# MODULATOR.net
KiCad netlist of a schematic drawn in Altium Designer
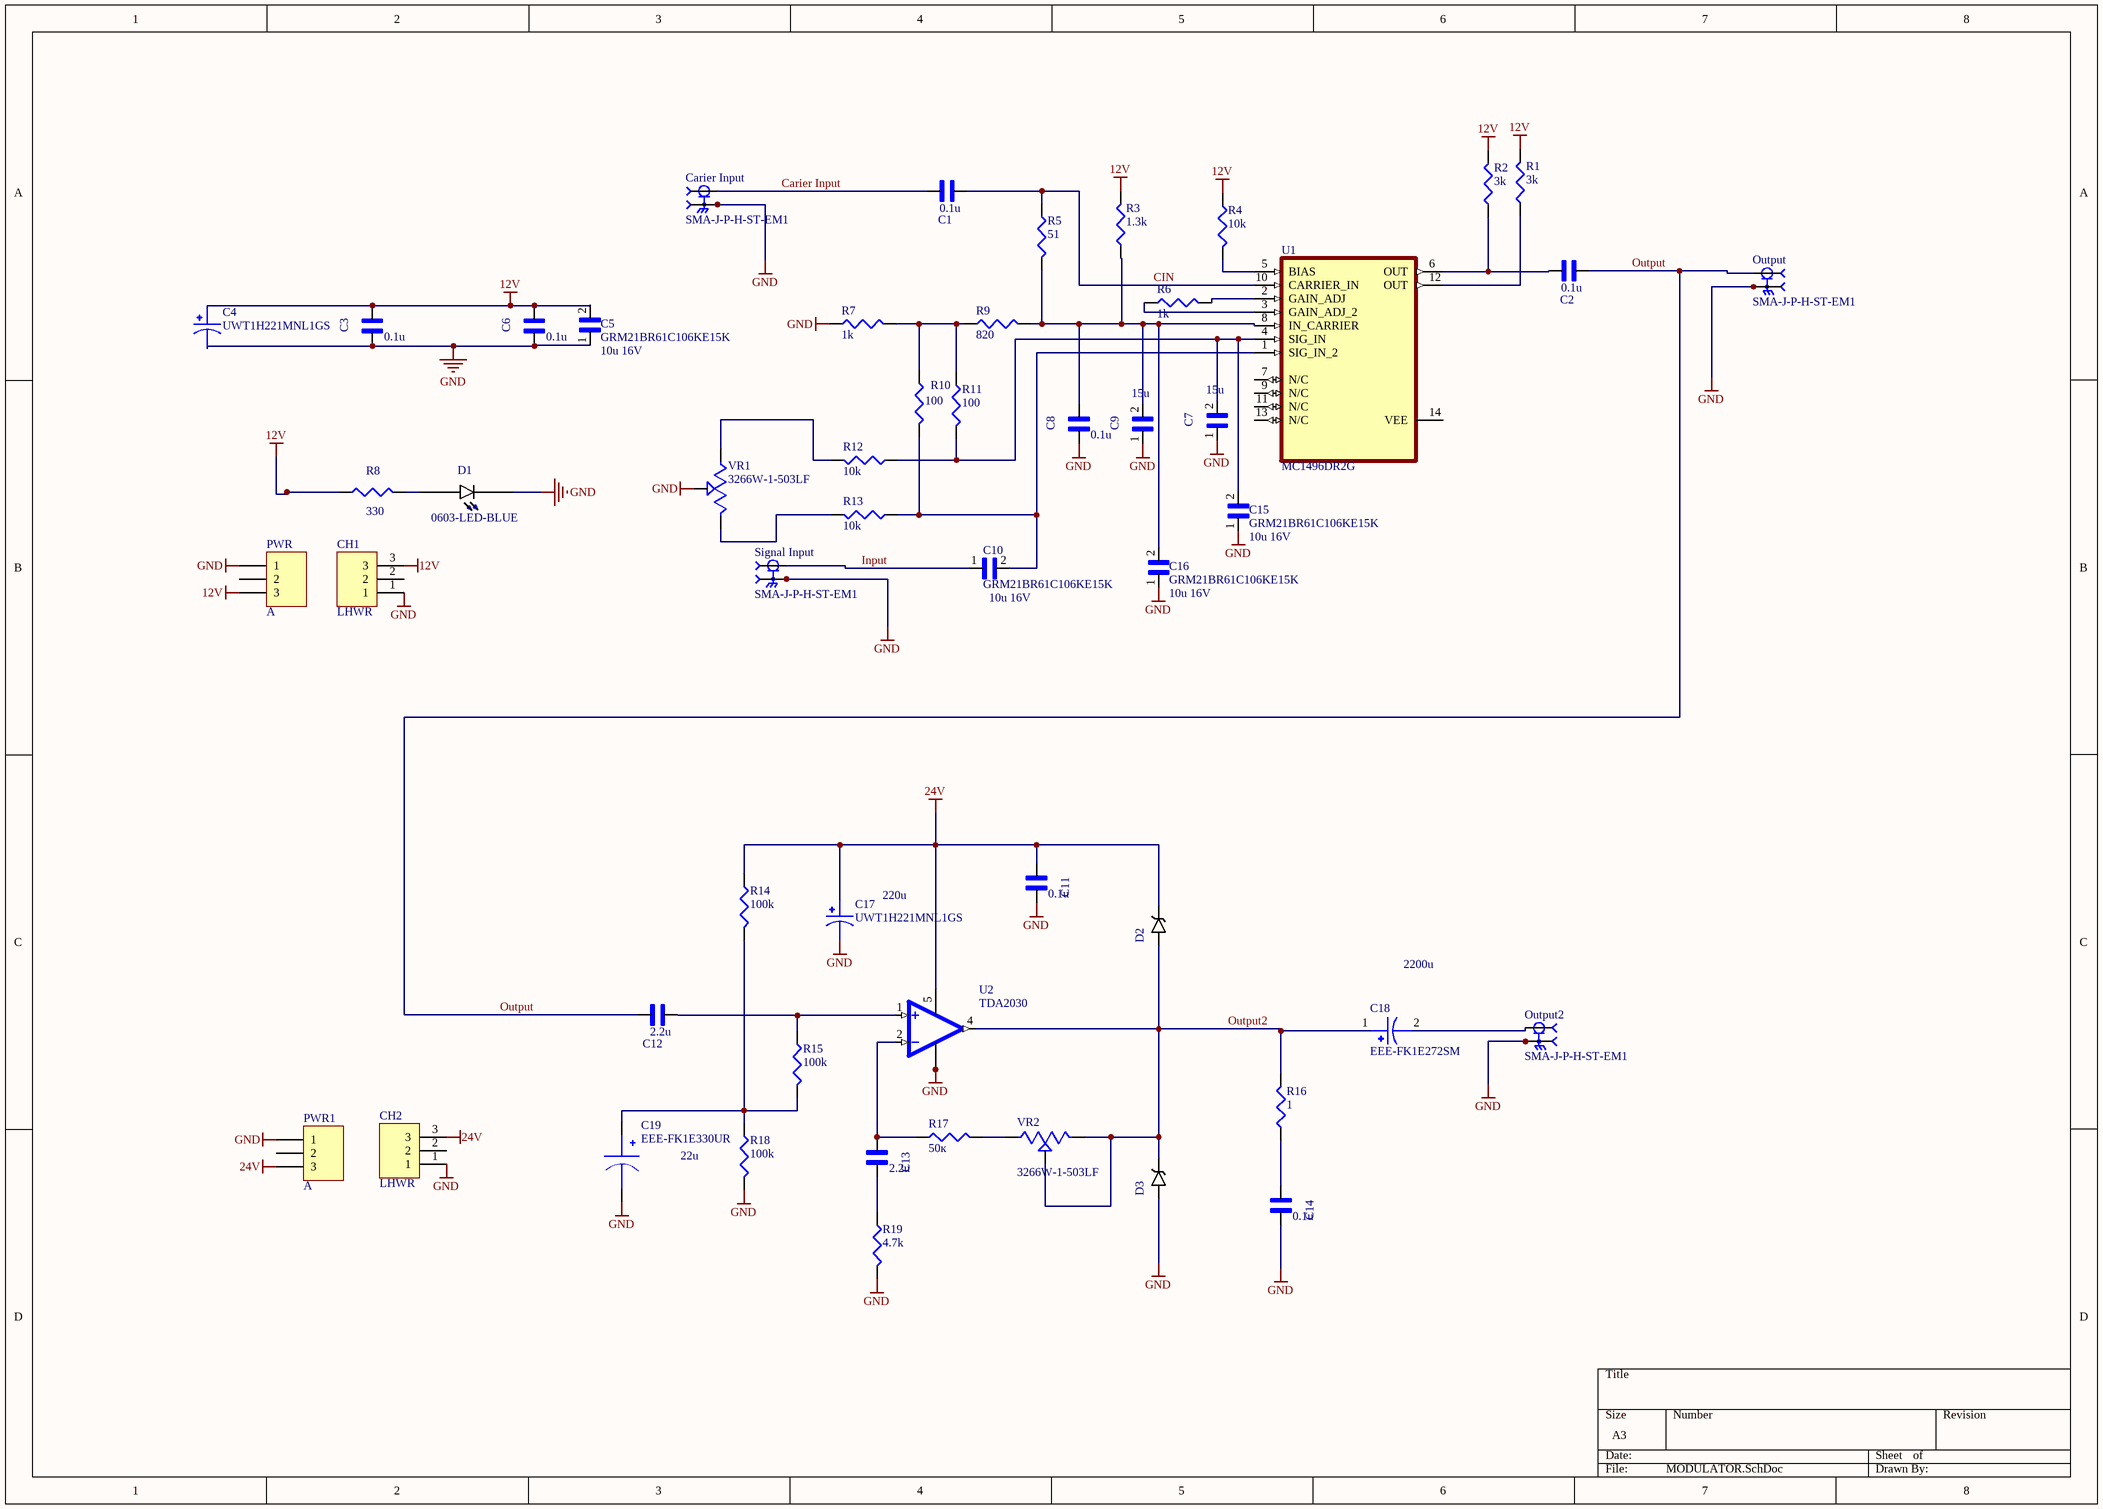
[diagram p0: MODULATOR.SchDoc]

(export (version "E")
  (design (tool "Eeschema 10.0.6"))
  (components
    (comp (ref "C1")
      (value "0.1u")
      (footprint "*CAPC1608X90")
      (description "Cap Thin Film 0.1uf 50v 0603")
      (fields (field (name "MF") "AVX") (field (name "MP") "GX035C104MAT2-500"))
      (libsource (lib "lib") (part "GX035C104MAT2-500"))
    )
    (comp (ref "C2")
      (value "0.1u")
      (footprint "*CAPC1608X90")
      (description "Cap Thin Film 0.1uf 50v 0603")
      (fields (field (name "MF") "AVX") (field (name "MP") "GX035C104MAT2-500"))
      (libsource (lib "lib") (part "GX035C104MAT2-500"))
    )
    (comp (ref "C3")
      (value "0.1u")
      (footprint "*CAPC1608X90")
      (description "Cap Thin Film 0.1uf 50v 0603")
      (fields (field (name "MF") "AVX") (field (name "MP") "GX035C104MAT2-500 or CL10B104JB8NNNC"))
      (libsource (lib "lib") (part "GX035C104MAT2-500"))
    )
    (comp (ref "C4")
      (value "UWT1H221MNL1GS")
      (footprint "CAPAE1030X1080N_UWT1H221MNL1GS")
      (description "220ВµF 50V Aluminum Electrolytic Capacitors Radial, Can - SMD 5000 Hrs @ 105В°C")
      (fields (field (name "MF") "{'manufacturer': u'Nichicon'}"))
      (libsource (lib "SnapEDA_Library") (part "UWT1H221MNL1GS"))
    )
    (comp (ref "C5")
      (value "GRM21BR61C106KE15K")
      (footprint "CAPC2012X135N")
      (fields (field (name "MF") "{'manufacturer': u'Murata'}") (field (name "ALTIUM_VALUE") "10u 16V"))
      (libsource (lib "") (part "GRM21BR61C106KE15K_1"))
    )
    (comp (ref "C6")
      (value "0.1u")
      (footprint "*CAPC1608X90")
      (description "Cap Thin Film 0.1uf 50v 0603")
      (fields (field (name "MF") "AVX") (field (name "MP") "GX035C104MAT2-500 or CL10B104JB8NNNC"))
      (libsource (lib "lib") (part "GX035C104MAT2-500"))
    )
    (comp (ref "C7")
      (value "15u")
      (footprint "*CAPC3216X125N")
      (description "Multilayer Ceramic Capacitor, GRM Series, 47 - F, - 10%, X5R, 10 V, 1206 [3216 Metric]")
      (fields (field (name "MF") "Murata Electronics") (field (name "MP") "GRM31CR61A476KE15L"))
      (libsource (lib "lib") (part "GRM31CR61A476KE15L"))
    )
    (comp (ref "C8")
      (value "0.1u")
      (footprint "*CAPC1608X90")
      (description "Cap Thin Film 0.1uf 50v 0603")
      (fields (field (name "MF") "AVX") (field (name "MP") "GX035C104MAT2-500"))
      (libsource (lib "lib") (part "GX035C104MAT2-500"))
    )
    (comp (ref "C9")
      (value "15u")
      (footprint "*CAPC3216X125N")
      (description "Multilayer Ceramic Capacitor, GRM Series, 47 - F, - 10%, X5R, 10 V, 1206 [3216 Metric]")
      (fields (field (name "MF") "Murata Electronics") (field (name "MP") "GRM31CR61A476KE15L"))
      (libsource (lib "lib") (part "GRM31CR61A476KE15L"))
    )
    (comp (ref "C10")
      (value "GRM21BR61C106KE15K")
      (footprint "CAPC2012X135N")
      (fields (field (name "MF") "{'manufacturer': u'Murata'}") (field (name "ALTIUM_VALUE") "10u 16V"))
      (libsource (lib "SnapEDA_Library") (part "GRM21BR61C106KE15K"))
    )
    (comp (ref "C11")
      (value "0.1u")
      (footprint "*CAPC1608X90")
      (description "Cap Thin Film 0.1uf 50v 0603")
      (fields (field (name "MF") "AVX") (field (name "MP") "GX035C104MAT2-500"))
      (libsource (lib "lib") (part "GX035C104MAT2-500"))
    )
    (comp (ref "C12")
      (value "2.2u")
      (footprint "*CAP3216X125N")
      (description "1206 2.2 uF 50 V В±10% Tolerance X7R SMT Multilayer Ceramic Capacitor")
      (fields (field (name "MF") "Murata Electronics") (field (name "MP") "GRM31CR71H225KA88L"))
      (libsource (lib "lib") (part "GRM31CR71H225KA88L"))
    )
    (comp (ref "C13")
      (value "2.2u")
      (footprint "*CAP3216X125N")
      (description "1206 2.2 uF 50 V В±10% Tolerance X7R SMT Multilayer Ceramic Capacitor")
      (fields (field (name "MF") "Murata Electronics") (field (name "MP") "GRM31CR71H225KA88L"))
      (libsource (lib "lib") (part "GRM31CR71H225KA88L"))
    )
    (comp (ref "C14")
      (value "0.1u")
      (footprint "*CAPC1608X90")
      (description "Cap Thin Film 0.1uf 50v 0603")
      (fields (field (name "MF") "AVX") (field (name "MP") "GX035C104MAT2-500"))
      (libsource (lib "lib") (part "GX035C104MAT2-500"))
    )
    (comp (ref "C15")
      (value "GRM21BR61C106KE15K")
      (footprint "CAPC2012X135N")
      (fields (field (name "MF") "{'manufacturer': u'Murata'}") (field (name "ALTIUM_VALUE") "10u 16V"))
      (libsource (lib "") (part "GRM21BR61C106KE15K_1"))
    )
    (comp (ref "C16")
      (value "GRM21BR61C106KE15K")
      (footprint "CAPC2012X135N")
      (fields (field (name "MF") "{'manufacturer': u'Murata'}") (field (name "ALTIUM_VALUE") "10u 16V"))
      (libsource (lib "") (part "GRM21BR61C106KE15K_1"))
    )
    (comp (ref "C17")
      (value "UWT1H221MNL1GS")
      (footprint "CAPAE1030X1080N_UWT1H221MNL1GS")
      (description "220ВµF 50V Aluminum Electrolytic Capacitors Radial, Can - SMD 5000 Hrs @ 105В°C")
      (fields (field (name "MF") "{'manufacturer': u'Nichicon'}"))
      (libsource (lib "SnapEDA_Library") (part "UWT1H221MNL1GS"))
    )
    (comp (ref "C18")
      (value "EEE-FK1E272SM")
      (footprint "CAP_EEE-FK1E272SM")
      (description "CAP ALUM 2700UF 20% 25V SMD")
      (fields (field (name "MF") "{'manufacturer': u'Panasonic Electronic Components'}"))
      (libsource (lib "SnapEDA_Library") (part "EEE-FK1E272SM"))
    )
    (comp (ref "C19")
      (value "EEE-FK1E330UR")
      (footprint "SM_RADIAL_C")
      (fields (field (name "MF") "{'manufacturer': u'Panasonic Electronic'}"))
      (libsource (lib "SnapEDA_Library") (part "EEE-FK1E330UR"))
    )
    (comp (ref "Carier Input")
      (value "SMA-J-P-H-ST-EM1")
      (footprint "SAMTEC_SMA-J-P-H-ST-EM1")
      (description "SMA Connector Jack, Female Socket 50Ohm Board Edge, End Launch Solder")
      (fields (field (name "MF") "Samtec") (field (name "DIGI-KEY_PART_NUMBER") "SAM8857-ND"))
      (libsource (lib "lib") (part "SMA-J-P-H-ST-EM1"))
    )
    (comp (ref "CH1")
      (value "LHWR")
      (footprint "KF350-3p")
      (fields (field (name "DESIGNER:") "Hamed Jafarzadeh - www.R2T.ir"))
      (libsource (lib "R2T Team Library") (part "Connector 3Pin"))
    )
    (comp (ref "CH2")
      (value "LHWR")
      (footprint "KF350-3p")
      (fields (field (name "DESIGNER:") "Hamed Jafarzadeh - www.R2T.ir"))
      (libsource (lib "R2T Team Library") (part "Connector 3Pin"))
    )
    (comp (ref "D1")
      (value "0603-LED-BLUE")
      (footprint "*LEDM1608X80_LTE-C1906R-14(Primary)")
      (description "LED IrLED Chip LED 2-Pin SMD T/R")
      (libsource (lib "lib") (part "LTE-C1906R-14"))
    )
    (comp (ref "D2")
      (value "SK56")
      (footprint "*SMB_P6SMB62AT3G(Primary)")
      (description "Диод Шоттки 5А 60В [SMB / DO-214AA]")
      (fields (field (name "MF") "Littelfuse Inc."))
      (libsource (lib "lib") (part "SK56"))
    )
    (comp (ref "D3")
      (value "SK56")
      (footprint "*SMB_P6SMB62AT3G(Primary)")
      (description "Диод Шоттки 5А 60В [SMB / DO-214AA]")
      (fields (field (name "MF") "Littelfuse Inc."))
      (libsource (lib "lib") (part "SK56"))
    )
    (comp (ref "Output")
      (value "SMA-J-P-H-ST-EM1")
      (footprint "SAMTEC_SMA-J-P-H-ST-EM1")
      (description "SMA Connector Jack, Female Socket 50Ohm Board Edge, End Launch Solder")
      (fields (field (name "MF") "Samtec") (field (name "DIGI-KEY_PART_NUMBER") "SAM8857-ND"))
      (libsource (lib "lib") (part "SMA-J-P-H-ST-EM1"))
    )
    (comp (ref "Output2")
      (value "SMA-J-P-H-ST-EM1")
      (footprint "SAMTEC_SMA-J-P-H-ST-EM1")
      (description "SMA Connector Jack, Female Socket 50Ohm Board Edge, End Launch Solder")
      (fields (field (name "MF") "Samtec") (field (name "DIGI-KEY_PART_NUMBER") "SAM8857-ND"))
      (libsource (lib "lib") (part "SMA-J-P-H-ST-EM1"))
    )
    (comp (ref "PWR")
      (value "A")
      (footprint "HDR Side 3 pin")
      (description "Header, 4-Pin")
      (fields (field (name "MF") "Connfly electronic (Zhenqin)") (field (name "MP") "PLS-3 (DS1021-1x3)"))
      (libsource (lib "DC_DC") (part "Header 3"))
    )
    (comp (ref "PWR1")
      (value "A")
      (footprint "HDR Side 3 pin")
      (description "Header, 4-Pin")
      (fields (field (name "MF") "Connfly electronic (Zhenqin)") (field (name "MP") "PLS-3 (DS1021-1x3)"))
      (libsource (lib "DC_DC") (part "Header 3"))
    )
    (comp (ref "R1")
      (value "3k")
      (footprint "J1-0603")
      (description "Resistor")
      (fields (field (name "MP") "RC0603FR-07330RL") (field (name "Comment") "Res3"))
      (libsource (lib "Miscellaneous Devices") (part "Res3"))
    )
    (comp (ref "R2")
      (value "3k")
      (footprint "J1-0603")
      (description "Resistor")
      (fields (field (name "MP") "RC0603FR-07330RL") (field (name "Comment") "Res3"))
      (libsource (lib "Miscellaneous Devices") (part "Res3"))
    )
    (comp (ref "R3")
      (value "1.3k")
      (footprint "J1-0603")
      (description "Resistor")
      (fields (field (name "MP") "RC0603FR-07330RL") (field (name "Comment") "Res3"))
      (libsource (lib "Miscellaneous Devices") (part "Res3"))
    )
    (comp (ref "R4")
      (value "10k")
      (footprint "J1-0603")
      (description "10 kOhms 1 0.1 W 1 10 W Chip Resistor 0603 1608 Metric Thick Film")
      (fields (field (name "MF") "Yageo or NXP") (field (name "MP") "10K 1% 0603"))
      (libsource (lib "CAN_NODE_MINI") (part "RC0603FR-0710KL"))
    )
    (comp (ref "R5")
      (value "51")
      (footprint "J1-0603")
      (description "Resistor")
      (fields (field (name "MP") "RC0603FR-07330RL") (field (name "Comment") "Res3"))
      (libsource (lib "Miscellaneous Devices") (part "Res3"))
    )
    (comp (ref "R6")
      (value "1k")
      (footprint "J1-0603")
      (description "Resistor")
      (fields (field (name "MP") "RC0603FR-07330RL") (field (name "Comment") "Res3"))
      (libsource (lib "Miscellaneous Devices") (part "Res3"))
    )
    (comp (ref "R7")
      (value "1k")
      (footprint "J1-0603")
      (description "Resistor")
      (fields (field (name "MP") "RC0603FR-07330RL") (field (name "Comment") "Res3"))
      (libsource (lib "Miscellaneous Devices") (part "Res3"))
    )
    (comp (ref "R8")
      (value "330")
      (footprint "J1-0603")
      (description "Resistor")
      (fields (field (name "MP") "RC0603FR-07330RL") (field (name "Comment") "Res3"))
      (libsource (lib "Miscellaneous Devices") (part "Res3"))
    )
    (comp (ref "R9")
      (value "820")
      (footprint "J1-0603")
      (description "Resistor")
      (fields (field (name "MP") "RC0603FR-07330RL") (field (name "Comment") "Res3"))
      (libsource (lib "Miscellaneous Devices") (part "Res3"))
    )
    (comp (ref "R10")
      (value "100")
      (footprint "J1-0603")
      (description "Resistor")
      (fields (field (name "MP") "RC0603FR-07330RL") (field (name "Comment") "Res3"))
      (libsource (lib "Miscellaneous Devices") (part "Res3"))
    )
    (comp (ref "R11")
      (value "100")
      (footprint "J1-0603")
      (description "Resistor")
      (fields (field (name "MP") "RC0603FR-07330RL") (field (name "Comment") "Res3"))
      (libsource (lib "Miscellaneous Devices") (part "Res3"))
    )
    (comp (ref "R12")
      (value "10k")
      (footprint "J1-0603")
      (description "10 kOhms 1 0.1 W 1 10 W Chip Resistor 0603 1608 Metric Thick Film")
      (fields (field (name "MF") "Yageo or NXP") (field (name "MP") "10K 1% 0603"))
      (libsource (lib "CAN_NODE_MINI") (part "RC0603FR-0710KL"))
    )
    (comp (ref "R13")
      (value "10k")
      (footprint "J1-0603")
      (description "10 kOhms 1 0.1 W 1 10 W Chip Resistor 0603 1608 Metric Thick Film")
      (fields (field (name "MF") "Yageo or NXP") (field (name "MP") "10K 1% 0603"))
      (libsource (lib "CAN_NODE_MINI") (part "RC0603FR-0710KL"))
    )
    (comp (ref "R14")
      (value "100k")
      (footprint "J1-0603")
      (description "10 kOhms 1 0.1 W 1 10 W Chip Resistor 0603 1608 Metric Thick Film")
      (fields (field (name "MF") "Yageo or NXP") (field (name "MP") "10K 1% 0603"))
      (libsource (lib "CAN_NODE_MINI") (part "RC0603FR-0710KL"))
    )
    (comp (ref "R15")
      (value "100k")
      (footprint "J1-0603")
      (description "10 kOhms 1 0.1 W 1 10 W Chip Resistor 0603 1608 Metric Thick Film")
      (fields (field (name "MF") "Yageo or NXP") (field (name "MP") "10K 1% 0603"))
      (libsource (lib "CAN_NODE_MINI") (part "RC0603FR-0710KL"))
    )
    (comp (ref "R16")
      (value "1")
      (footprint "J1-0603")
      (description "10 kOhms 1 0.1 W 1 10 W Chip Resistor 0603 1608 Metric Thick Film")
      (fields (field (name "MF") "Yageo or NXP") (field (name "MP") "10K 1% 0603"))
      (libsource (lib "CAN_NODE_MINI") (part "RC0603FR-0710KL"))
    )
    (comp (ref "R17")
      (value "50к")
      (footprint "J1-0603")
      (description "10 kOhms 1 0.1 W 1 10 W Chip Resistor 0603 1608 Metric Thick Film")
      (fields (field (name "MF") "Yageo or NXP") (field (name "MP") "10K 1% 0603"))
      (libsource (lib "CAN_NODE_MINI") (part "RC0603FR-0710KL"))
    )
    (comp (ref "R18")
      (value "100k")
      (footprint "J1-0603")
      (description "10 kOhms 1 0.1 W 1 10 W Chip Resistor 0603 1608 Metric Thick Film")
      (fields (field (name "MF") "Yageo or NXP") (field (name "MP") "10K 1% 0603"))
      (libsource (lib "CAN_NODE_MINI") (part "RC0603FR-0710KL"))
    )
    (comp (ref "R19")
      (value "4.7k")
      (footprint "J1-0603")
      (description "10 kOhms 1 0.1 W 1 10 W Chip Resistor 0603 1608 Metric Thick Film")
      (fields (field (name "MF") "Yageo or NXP") (field (name "MP") "10K 1% 0603"))
      (libsource (lib "CAN_NODE_MINI") (part "RC0603FR-0710KL"))
    )
    (comp (ref "Signal Input")
      (value "SMA-J-P-H-ST-EM1")
      (footprint "SAMTEC_SMA-J-P-H-ST-EM1")
      (description "SMA Connector Jack, Female Socket 50Ohm Board Edge, End Launch Solder")
      (fields (field (name "MF") "Samtec") (field (name "DIGI-KEY_PART_NUMBER") "SAM8857-ND"))
      (libsource (lib "lib") (part "SMA-J-P-H-ST-EM1"))
    )
    (comp (ref "U1")
      (value "MC1496DR2G")
      (footprint "SOIC127P600X175-14N")
      (fields (field (name "MF") "{'manufacturer': u'ON Semiconductor'}"))
      (libsource (lib "SnapEDA_Library") (part "MC1496DR2G"))
    )
    (comp (ref "U2")
      (value "TDA2030")
      (footprint "TO170P1580X1040X480-5")
      (description "14 W hi-fi audio amplifier")
      (fields (field (name "MF") "{'manufacturer': u'STMicroelectronics'}"))
      (libsource (lib "SnapEDA_Library") (part "TDA2030"))
    )
    (comp (ref "VR1")
      (value "3266W-1-503LF")
      (footprint "TRIM_3266W-1-503LF")
      (description "Res Cermet Trimmer 1K Ohm 10% 1/4W 12(Elec)Turn 1.78mm (6.71 X 4.5 X 8.26mm) Pin Thru-Hole Tube")
      (fields (field (name "MF") "{'manufacturer': u'Bourns'}"))
      (libsource (lib "SnapEDA_Library") (part "3266W-1-503LF"))
    )
    (comp (ref "VR2")
      (value "3266W-1-503LF")
      (footprint "TRIM_3266W-1-503LF")
      (description "Res Cermet Trimmer 1K Ohm 10% 1/4W 12(Elec)Turn 1.78mm (6.71 X 4.5 X 8.26mm) Pin Thru-Hole Tube")
      (fields (field (name "MF") "{'manufacturer': u'Bourns'}"))
      (libsource (lib "SnapEDA_Library") (part "3266W-1-503LF"))
    )
  )
  (nets
    (net (code "1") (name "/CIN") (class "Default")
      (node (ref "C1") (pin "2") (pinfunction "2_2") (pintype "passive"))
      (node (ref "R5") (pin "1") (pinfunction "1_1") (pintype "passive"))
      (node (ref "U1") (pin "10") (pinfunction "CARRIER_IN_10") (pintype "input"))
    )
    (net (code "2") (name "/Carier Input") (class "Default")
      (node (ref "C1") (pin "1") (pinfunction "1_1") (pintype "passive"))
      (node (ref "Carier Input") (pin "1") (pinfunction "1_1") (pintype "passive"))
    )
    (net (code "3") (name "/Input") (class "Default")
      (node (ref "C10") (pin "1") (pinfunction "1_1") (pintype "passive"))
      (node (ref "Signal Input") (pin "1") (pinfunction "1_1") (pintype "passive"))
    )
    (net (code "4") (name "/Output") (class "Default")
      (node (ref "C12") (pin "1") (pinfunction "1_1") (pintype "passive"))
      (node (ref "C2") (pin "2") (pinfunction "2_2") (pintype "passive"))
      (node (ref "Output") (pin "1") (pinfunction "1_1") (pintype "passive"))
    )
    (net (code "5") (name "/Output2") (class "Default")
      (node (ref "C18") (pin "1") (pinfunction "1_1") (pintype "passive"))
      (node (ref "D2") (pin "A") (pinfunction "A_A") (pintype "power_in"))
      (node (ref "D3") (pin "C") (pinfunction "C_C") (pintype "power_in"))
      (node (ref "R16") (pin "2") (pinfunction "2_2") (pintype "passive"))
      (node (ref "U2") (pin "4") (pinfunction "OUTPUT_4") (pintype "output"))
      (node (ref "VR2") (pin "2") (pinfunction "WIPER_2") (pintype "passive"))
      (node (ref "VR2") (pin "3") (pinfunction "CW_3") (pintype "passive"))
    )
    (net (code "6") (name "12V") (class "Default")
      (node (ref "C3") (pin "1") (pinfunction "1_1") (pintype "passive"))
      (node (ref "C4") (pin "1") (pinfunction "1_1") (pintype "passive"))
      (node (ref "C5") (pin "2") (pinfunction "2_2") (pintype "passive"))
      (node (ref "C6") (pin "1") (pinfunction "1_1") (pintype "passive"))
      (node (ref "CH1") (pin "3") (pinfunction "3_3") (pintype "passive"))
      (node (ref "PWR") (pin "3") (pinfunction "3_3") (pintype "passive"))
      (node (ref "R1") (pin "2") (pinfunction "2_2") (pintype "passive"))
      (node (ref "R2") (pin "2") (pinfunction "2_2") (pintype "passive"))
      (node (ref "R3") (pin "2") (pinfunction "2_2") (pintype "passive"))
      (node (ref "R4") (pin "1") (pinfunction "1_1") (pintype "passive"))
      (node (ref "R8") (pin "1") (pinfunction "1_1") (pintype "passive"))
    )
    (net (code "7") (name "24V") (class "Default")
      (node (ref "C11") (pin "2") (pinfunction "2_2") (pintype "passive"))
      (node (ref "C17") (pin "1") (pinfunction "1_1") (pintype "passive"))
      (node (ref "CH2") (pin "3") (pinfunction "3_3") (pintype "passive"))
      (node (ref "D2") (pin "C") (pinfunction "C_C") (pintype "power_in"))
      (node (ref "PWR1") (pin "3") (pinfunction "3_3") (pintype "passive"))
      (node (ref "R14") (pin "1") (pinfunction "1_1") (pintype "passive"))
      (node (ref "U2") (pin "5") (pinfunction "+VS_5") (pintype "power_in"))
    )
    (net (code "8") (name "GND") (class "Default")
      (node (ref "C11") (pin "1") (pinfunction "1_1") (pintype "passive"))
      (node (ref "C14") (pin "1") (pinfunction "1_1") (pintype "passive"))
      (node (ref "C15") (pin "1") (pinfunction "1_1") (pintype "passive"))
      (node (ref "C16") (pin "1") (pinfunction "1_1") (pintype "passive"))
      (node (ref "C17") (pin "2") (pinfunction "2_2") (pintype "passive"))
      (node (ref "C19") (pin "2") (pinfunction "NEG_2") (pintype "passive"))
      (node (ref "C3") (pin "2") (pinfunction "2_2") (pintype "passive"))
      (node (ref "C4") (pin "2") (pinfunction "2_2") (pintype "passive"))
      (node (ref "C5") (pin "1") (pinfunction "1_1") (pintype "passive"))
      (node (ref "C6") (pin "2") (pinfunction "2_2") (pintype "passive"))
      (node (ref "C7") (pin "1") (pinfunction "1_1") (pintype "passive"))
      (node (ref "C8") (pin "2") (pinfunction "2_2") (pintype "passive"))
      (node (ref "C9") (pin "1") (pinfunction "1_1") (pintype "passive"))
      (node (ref "CH1") (pin "1") (pinfunction "1_1") (pintype "passive"))
      (node (ref "CH2") (pin "1") (pinfunction "1_1") (pintype "passive"))
      (node (ref "Carier Input") (pin "2_1") (pinfunction "2_2_1") (pintype "passive"))
      (node (ref "Carier Input") (pin "2_2") (pinfunction "2_2_2") (pintype "passive"))
      (node (ref "Carier Input") (pin "3_1") (pinfunction "2_3_1") (pintype "passive"))
      (node (ref "Carier Input") (pin "3_2") (pinfunction "2_3_2") (pintype "passive"))
      (node (ref "D1") (pin "C") (pinfunction "C_C") (pintype "passive"))
      (node (ref "D3") (pin "A") (pinfunction "A_A") (pintype "power_in"))
      (node (ref "Output") (pin "2_1") (pinfunction "2_2_1") (pintype "passive"))
      (node (ref "Output") (pin "2_2") (pinfunction "2_2_2") (pintype "passive"))
      (node (ref "Output") (pin "3_1") (pinfunction "2_3_1") (pintype "passive"))
      (node (ref "Output") (pin "3_2") (pinfunction "2_3_2") (pintype "passive"))
      (node (ref "Output2") (pin "2_1") (pinfunction "2_2_1") (pintype "passive"))
      (node (ref "Output2") (pin "2_2") (pinfunction "2_2_2") (pintype "passive"))
      (node (ref "Output2") (pin "3_1") (pinfunction "2_3_1") (pintype "passive"))
      (node (ref "Output2") (pin "3_2") (pinfunction "2_3_2") (pintype "passive"))
      (node (ref "PWR") (pin "1") (pinfunction "1_1") (pintype "passive"))
      (node (ref "PWR1") (pin "1") (pinfunction "1_1") (pintype "passive"))
      (node (ref "R18") (pin "2") (pinfunction "2_2") (pintype "passive"))
      (node (ref "R19") (pin "2") (pinfunction "2_2") (pintype "passive"))
      (node (ref "R7") (pin "1") (pinfunction "1_1") (pintype "passive"))
      (node (ref "Signal Input") (pin "2_1") (pinfunction "2_2_1") (pintype "passive"))
      (node (ref "Signal Input") (pin "2_2") (pinfunction "2_2_2") (pintype "passive"))
      (node (ref "Signal Input") (pin "3_1") (pinfunction "2_3_1") (pintype "passive"))
      (node (ref "Signal Input") (pin "3_2") (pinfunction "2_3_2") (pintype "passive"))
      (node (ref "U2") (pin "3") (pinfunction "-VS_3") (pintype "power_in"))
      (node (ref "U2") (pin "6") (pinfunction "-VS_6") (pintype "power_in"))
      (node (ref "U2") (pin "6.1") (pinfunction "-VS_6.1") (pintype "power_in"))
      (node (ref "VR1") (pin "2") (pinfunction "WIPER_2") (pintype "passive"))
    )
    (net (code "9") (name "Net-(C2-Pad1)") (class "Default")
      (node (ref "C2") (pin "1") (pinfunction "1_1") (pintype "passive"))
      (node (ref "R2") (pin "1") (pinfunction "1_1") (pintype "passive"))
      (node (ref "U1") (pin "6") (pinfunction "OUT_6") (pintype "output"))
    )
    (net (code "10") (name "Net-(C13-Pad1)") (class "Default")
      (node (ref "C13") (pin "1") (pinfunction "1_1") (pintype "passive"))
      (node (ref "R19") (pin "1") (pinfunction "1_1") (pintype "passive"))
    )
    (net (code "11") (name "Net-(C14-Pad2)") (class "Default")
      (node (ref "C14") (pin "2") (pinfunction "2_2") (pintype "passive"))
      (node (ref "R16") (pin "1") (pinfunction "1_1") (pintype "passive"))
    )
    (net (code "12") (name "Net-(C18-Pad2)") (class "Default")
      (node (ref "C18") (pin "2") (pinfunction "2_2") (pintype "passive"))
      (node (ref "Output2") (pin "1") (pinfunction "1_1") (pintype "passive"))
    )
    (net (code "13") (name "Net-(C19-POS)") (class "Default")
      (node (ref "C19") (pin "1") (pinfunction "POS_1") (pintype "passive"))
      (node (ref "R14") (pin "2") (pinfunction "2_2") (pintype "passive"))
      (node (ref "R15") (pin "2") (pinfunction "2_2") (pintype "passive"))
      (node (ref "R18") (pin "1") (pinfunction "1_1") (pintype "passive"))
    )
    (net (code "14") (name "Net-(D1-PadA)") (class "Default")
      (node (ref "D1") (pin "A") (pinfunction "A_A") (pintype "passive"))
      (node (ref "R8") (pin "2") (pinfunction "2_2") (pintype "passive"))
    )
    (net (code "15") (name "Net-(R1-Pad1)") (class "Default")
      (node (ref "R1") (pin "1") (pinfunction "1_1") (pintype "passive"))
      (node (ref "U1") (pin "12") (pinfunction "OUT_12") (pintype "output"))
    )
    (net (code "16") (name "Net-(R10-Pad1)") (class "Default")
      (node (ref "R10") (pin "1") (pinfunction "1_1") (pintype "passive"))
      (node (ref "R11") (pin "1") (pinfunction "1_1") (pintype "passive"))
      (node (ref "R7") (pin "2") (pinfunction "2_2") (pintype "passive"))
      (node (ref "R9") (pin "1") (pinfunction "1_1") (pintype "passive"))
    )
    (net (code "17") (name "Net-(U1-BIAS)") (class "Default")
      (node (ref "R4") (pin "2") (pinfunction "2_2") (pintype "passive"))
      (node (ref "U1") (pin "5") (pinfunction "BIAS_5") (pintype "input"))
    )
    (net (code "18") (name "Net-(U1-GAIN_ADJ)") (class "Default")
      (node (ref "R6") (pin "2") (pinfunction "2_2") (pintype "passive"))
      (node (ref "U1") (pin "2") (pinfunction "GAIN_ADJ_2") (pintype "input"))
    )
    (net (code "19") (name "Net-(U1-GAIN_ADJ_2)") (class "Default")
      (node (ref "R6") (pin "1") (pinfunction "1_1") (pintype "passive"))
      (node (ref "U1") (pin "3") (pinfunction "GAIN_ADJ_2_3") (pintype "input"))
    )
    (net (code "20") (name "Net-(U1-IN_CARRIER)") (class "Default")
      (node (ref "C16") (pin "2") (pinfunction "2_2") (pintype "passive"))
      (node (ref "C8") (pin "1") (pinfunction "1_1") (pintype "passive"))
      (node (ref "C9") (pin "2") (pinfunction "2_2") (pintype "passive"))
      (node (ref "R3") (pin "1") (pinfunction "1_1") (pintype "passive"))
      (node (ref "R5") (pin "2") (pinfunction "2_2") (pintype "passive"))
      (node (ref "R9") (pin "2") (pinfunction "2_2") (pintype "passive"))
      (node (ref "U1") (pin "8") (pinfunction "IN_CARRIER_8") (pintype "input"))
    )
    (net (code "21") (name "Net-(U1-SIG_IN)") (class "Default")
      (node (ref "C15") (pin "2") (pinfunction "2_2") (pintype "passive"))
      (node (ref "C7") (pin "2") (pinfunction "2_2") (pintype "passive"))
      (node (ref "R11") (pin "2") (pinfunction "2_2") (pintype "passive"))
      (node (ref "R12") (pin "1") (pinfunction "1_1") (pintype "passive"))
      (node (ref "U1") (pin "4") (pinfunction "SIG_IN_4") (pintype "input"))
    )
    (net (code "22") (name "Net-(U1-SIG_IN_2)") (class "Default")
      (node (ref "C10") (pin "2") (pinfunction "2_2") (pintype "passive"))
      (node (ref "R10") (pin "2") (pinfunction "2_2") (pintype "passive"))
      (node (ref "R13") (pin "1") (pinfunction "1_1") (pintype "passive"))
      (node (ref "U1") (pin "1") (pinfunction "SIG_IN_2_1") (pintype "input"))
    )
    (net (code "23") (name "Net-(U2-INV_INPUT)") (class "Default")
      (node (ref "C13") (pin "2") (pinfunction "2_2") (pintype "passive"))
      (node (ref "R17") (pin "1") (pinfunction "1_1") (pintype "passive"))
      (node (ref "U2") (pin "2") (pinfunction "INV_INPUT_2") (pintype "input"))
    )
    (net (code "24") (name "Net-(U2-NON_INV_INPUT)") (class "Default")
      (node (ref "C12") (pin "2") (pinfunction "2_2") (pintype "passive"))
      (node (ref "R15") (pin "1") (pinfunction "1_1") (pintype "passive"))
      (node (ref "U2") (pin "1") (pinfunction "NON_INV_INPUT_1") (pintype "input"))
    )
    (net (code "25") (name "Net-(VR1-CCW)") (class "Default")
      (node (ref "R12") (pin "2") (pinfunction "2_2") (pintype "passive"))
      (node (ref "VR1") (pin "1") (pinfunction "CCW_1") (pintype "passive"))
    )
    (net (code "26") (name "Net-(VR1-CW)") (class "Default")
      (node (ref "R13") (pin "2") (pinfunction "2_2") (pintype "passive"))
      (node (ref "VR1") (pin "3") (pinfunction "CW_3") (pintype "passive"))
    )
    (net (code "27") (name "Net-(VR2-CCW)") (class "Default")
      (node (ref "R17") (pin "2") (pinfunction "2_2") (pintype "passive"))
      (node (ref "VR2") (pin "1") (pinfunction "CCW_1") (pintype "passive"))
    )
    (net (code "28") (name "unconnected-(CH1-Pad2)") (class "Default")
      (node (ref "CH1") (pin "2") (pinfunction "2_2") (pintype "passive"))
    )
    (net (code "29") (name "unconnected-(CH2-Pad2)") (class "Default")
      (node (ref "CH2") (pin "2") (pinfunction "2_2") (pintype "passive"))
    )
    (net (code "30") (name "unconnected-(PWR-Pad2)") (class "Default")
      (node (ref "PWR") (pin "2") (pinfunction "2_2") (pintype "passive"))
    )
    (net (code "31") (name "unconnected-(PWR1-Pad2)") (class "Default")
      (node (ref "PWR1") (pin "2") (pinfunction "2_2") (pintype "passive"))
    )
    (net (code "32") (name "unconnected-(U1-N{slash}C-Pad7)") (class "Default")
      (node (ref "U1") (pin "7") (pinfunction "N/C_7") (pintype "bidirectional"))
    )
    (net (code "33") (name "unconnected-(U1-N{slash}C-Pad9)") (class "Default")
      (node (ref "U1") (pin "9") (pinfunction "N/C_9") (pintype "bidirectional"))
    )
    (net (code "34") (name "unconnected-(U1-N{slash}C-Pad11)") (class "Default")
      (node (ref "U1") (pin "11") (pinfunction "N/C_11") (pintype "bidirectional"))
    )
    (net (code "35") (name "unconnected-(U1-N{slash}C-Pad13)") (class "Default")
      (node (ref "U1") (pin "13") (pinfunction "N/C_13") (pintype "bidirectional"))
    )
    (net (code "36") (name "unconnected-(U1-VEE-Pad14)") (class "Default")
      (node (ref "U1") (pin "14") (pinfunction "VEE_14") (pintype "power_in"))
    )
  )
)
